# HPFREF1.net
KiCad netlist of a schematic drawn in Altium Designer
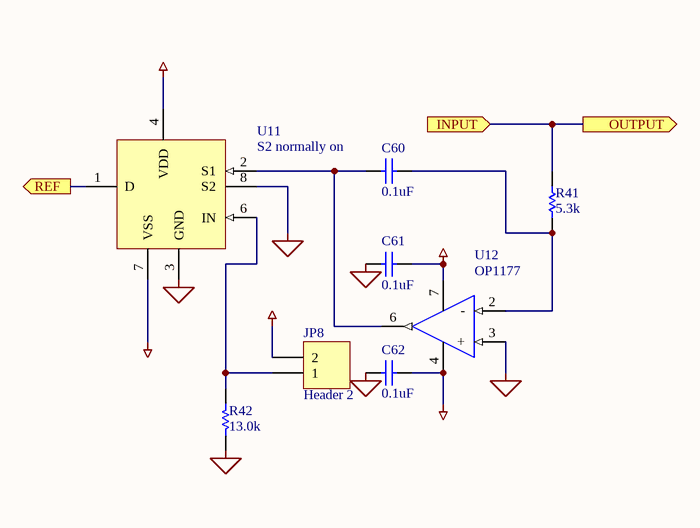
[diagram p0: HPFREF1.SCHDOC]

(export (version "E")
  (design (tool "Eeschema 10.0.6"))
  (components
    (comp (ref "C60")
      (value "0.1uF")
      (footprint "CC3216-1206")
      (description "Capacitor")
      (fields
        (field (name "MANUFACTURER") "Generic Components")
        (field (name "Comment") "Cap")
        (field (name "PUBLISHER") "Altium Limited")
      )
      (libsource (lib "Miscellaneous Devices") (part "Cap"))
    )
    (comp (ref "C61")
      (value "0.1uF")
      (footprint "CC1608-0603")
      (description "Capacitor")
      (fields
        (field (name "MANUFACTURER") "Generic Components")
        (field (name "Comment") "Cap")
        (field (name "PUBLISHER") "Altium Limited")
      )
      (libsource (lib "Miscellaneous Devices") (part "Cap"))
    )
    (comp (ref "C62")
      (value "0.1uF")
      (footprint "CC1608-0603")
      (description "Capacitor")
      (fields
        (field (name "MANUFACTURER") "Generic Components")
        (field (name "Comment") "Cap")
        (field (name "PUBLISHER") "Altium Limited")
      )
      (libsource (lib "Miscellaneous Devices") (part "Cap"))
    )
    (comp (ref "JP8")
      (value "Header 2")
      (footprint "HDR1X2")
      (description "Header, 2-Pin")
      (fields (field (name "MANUFACTURER") "Generic Components") (field (name "PUBLISHER") "Altium Limited"))
      (libsource (lib "Miscellaneous Connectors") (part "Header 2"))
    )
    (comp (ref "R41")
      (value "5.3k")
      (footprint "CC2012-0805")
      (description "Resistor")
      (fields
        (field (name "MANUFACTURER") "Generic Components")
        (field (name "Comment") "Res1")
        (field (name "PUBLISHER") "Altium Limited")
      )
      (libsource (lib "Miscellaneous Devices") (part "Res1"))
    )
    (comp (ref "R42")
      (value "13.0k")
      (footprint "CC2012-0805")
      (description "Resistor")
      (fields
        (field (name "MANUFACTURER") "Generic Components")
        (field (name "Comment") "Res1")
        (field (name "PUBLISHER") "Altium Limited")
      )
      (libsource (lib "Miscellaneous Devices") (part "Res1"))
    )
    (comp (ref "U11")
      (value "S2 normally on")
      (footprint "MSOP8")
      (description "Low RON SPDT Switch")
      (libsource (lib "My devices") (part "ADG619"))
    )
    (comp (ref "U12")
      (value "OP1177")
      (footprint "SO-G8/X.6")
      (description "AD Precision Low Noise, Low Input Bias Current Operational Amplifier")
      (libsource (lib "My devices") (part "OP1177"))
    )
  )
  (nets
    (net (code "1") (name "/INPUT") (class "Default")
      (node (ref "R41") (pin "1") (pinfunction "1_1") (pintype "passive"))
    )
    (net (code "2") (name "/REF") (class "Default")
      (node (ref "U11") (pin "1") (pinfunction "D_1") (pintype "passive"))
    )
    (net (code "3") (name "AGND") (class "Default")
      (node (ref "C61") (pin "1") (pinfunction "1_1") (pintype "passive"))
      (node (ref "C62") (pin "1") (pinfunction "1_1") (pintype "passive"))
      (node (ref "R42") (pin "1") (pinfunction "1_1") (pintype "passive"))
      (node (ref "U11") (pin "3") (pinfunction "GND_3") (pintype "power_in"))
      (node (ref "U11") (pin "8") (pinfunction "S2_8") (pintype "passive"))
      (node (ref "U12") (pin "3") (pinfunction "+_3") (pintype "input"))
    )
    (net (code "4") (name "AVDD") (class "Default")
      (node (ref "C61") (pin "2") (pinfunction "2_2") (pintype "passive"))
      (node (ref "JP8") (pin "2") (pinfunction "2_2") (pintype "passive"))
      (node (ref "U11") (pin "4") (pinfunction "VDD_4") (pintype "power_in"))
      (node (ref "U12") (pin "7") (pinfunction "+Vs_7") (pintype "power_in"))
    )
    (net (code "5") (name "AVSS") (class "Default")
      (node (ref "C62") (pin "2") (pinfunction "2_2") (pintype "passive"))
      (node (ref "U11") (pin "7") (pinfunction "VSS_7") (pintype "power_in"))
      (node (ref "U12") (pin "4") (pinfunction "-Vs_4") (pintype "power_in"))
    )
    (net (code "6") (name "Net-(U11-IN)") (class "Default")
      (node (ref "JP8") (pin "1") (pinfunction "1_1") (pintype "passive"))
      (node (ref "R42") (pin "2") (pinfunction "2_2") (pintype "passive"))
      (node (ref "U11") (pin "6") (pinfunction "IN_6") (pintype "input"))
    )
    (net (code "7") (name "Net-(U11-S1)") (class "Default")
      (node (ref "C60") (pin "2") (pinfunction "2_2") (pintype "passive"))
      (node (ref "U11") (pin "2") (pinfunction "S1_2") (pintype "input"))
      (node (ref "U12") (pin "6") (pinfunction "Out_6") (pintype "output"))
    )
    (net (code "8") (name "Net-(U12--)") (class "Default")
      (node (ref "C60") (pin "1") (pinfunction "1_1") (pintype "passive"))
      (node (ref "R41") (pin "2") (pinfunction "2_2") (pintype "passive"))
      (node (ref "U12") (pin "2") (pinfunction "-_2") (pintype "input"))
    )
  )
)
